# FPGA_2.net
KiCad netlist of a schematic drawn in Altium Designer
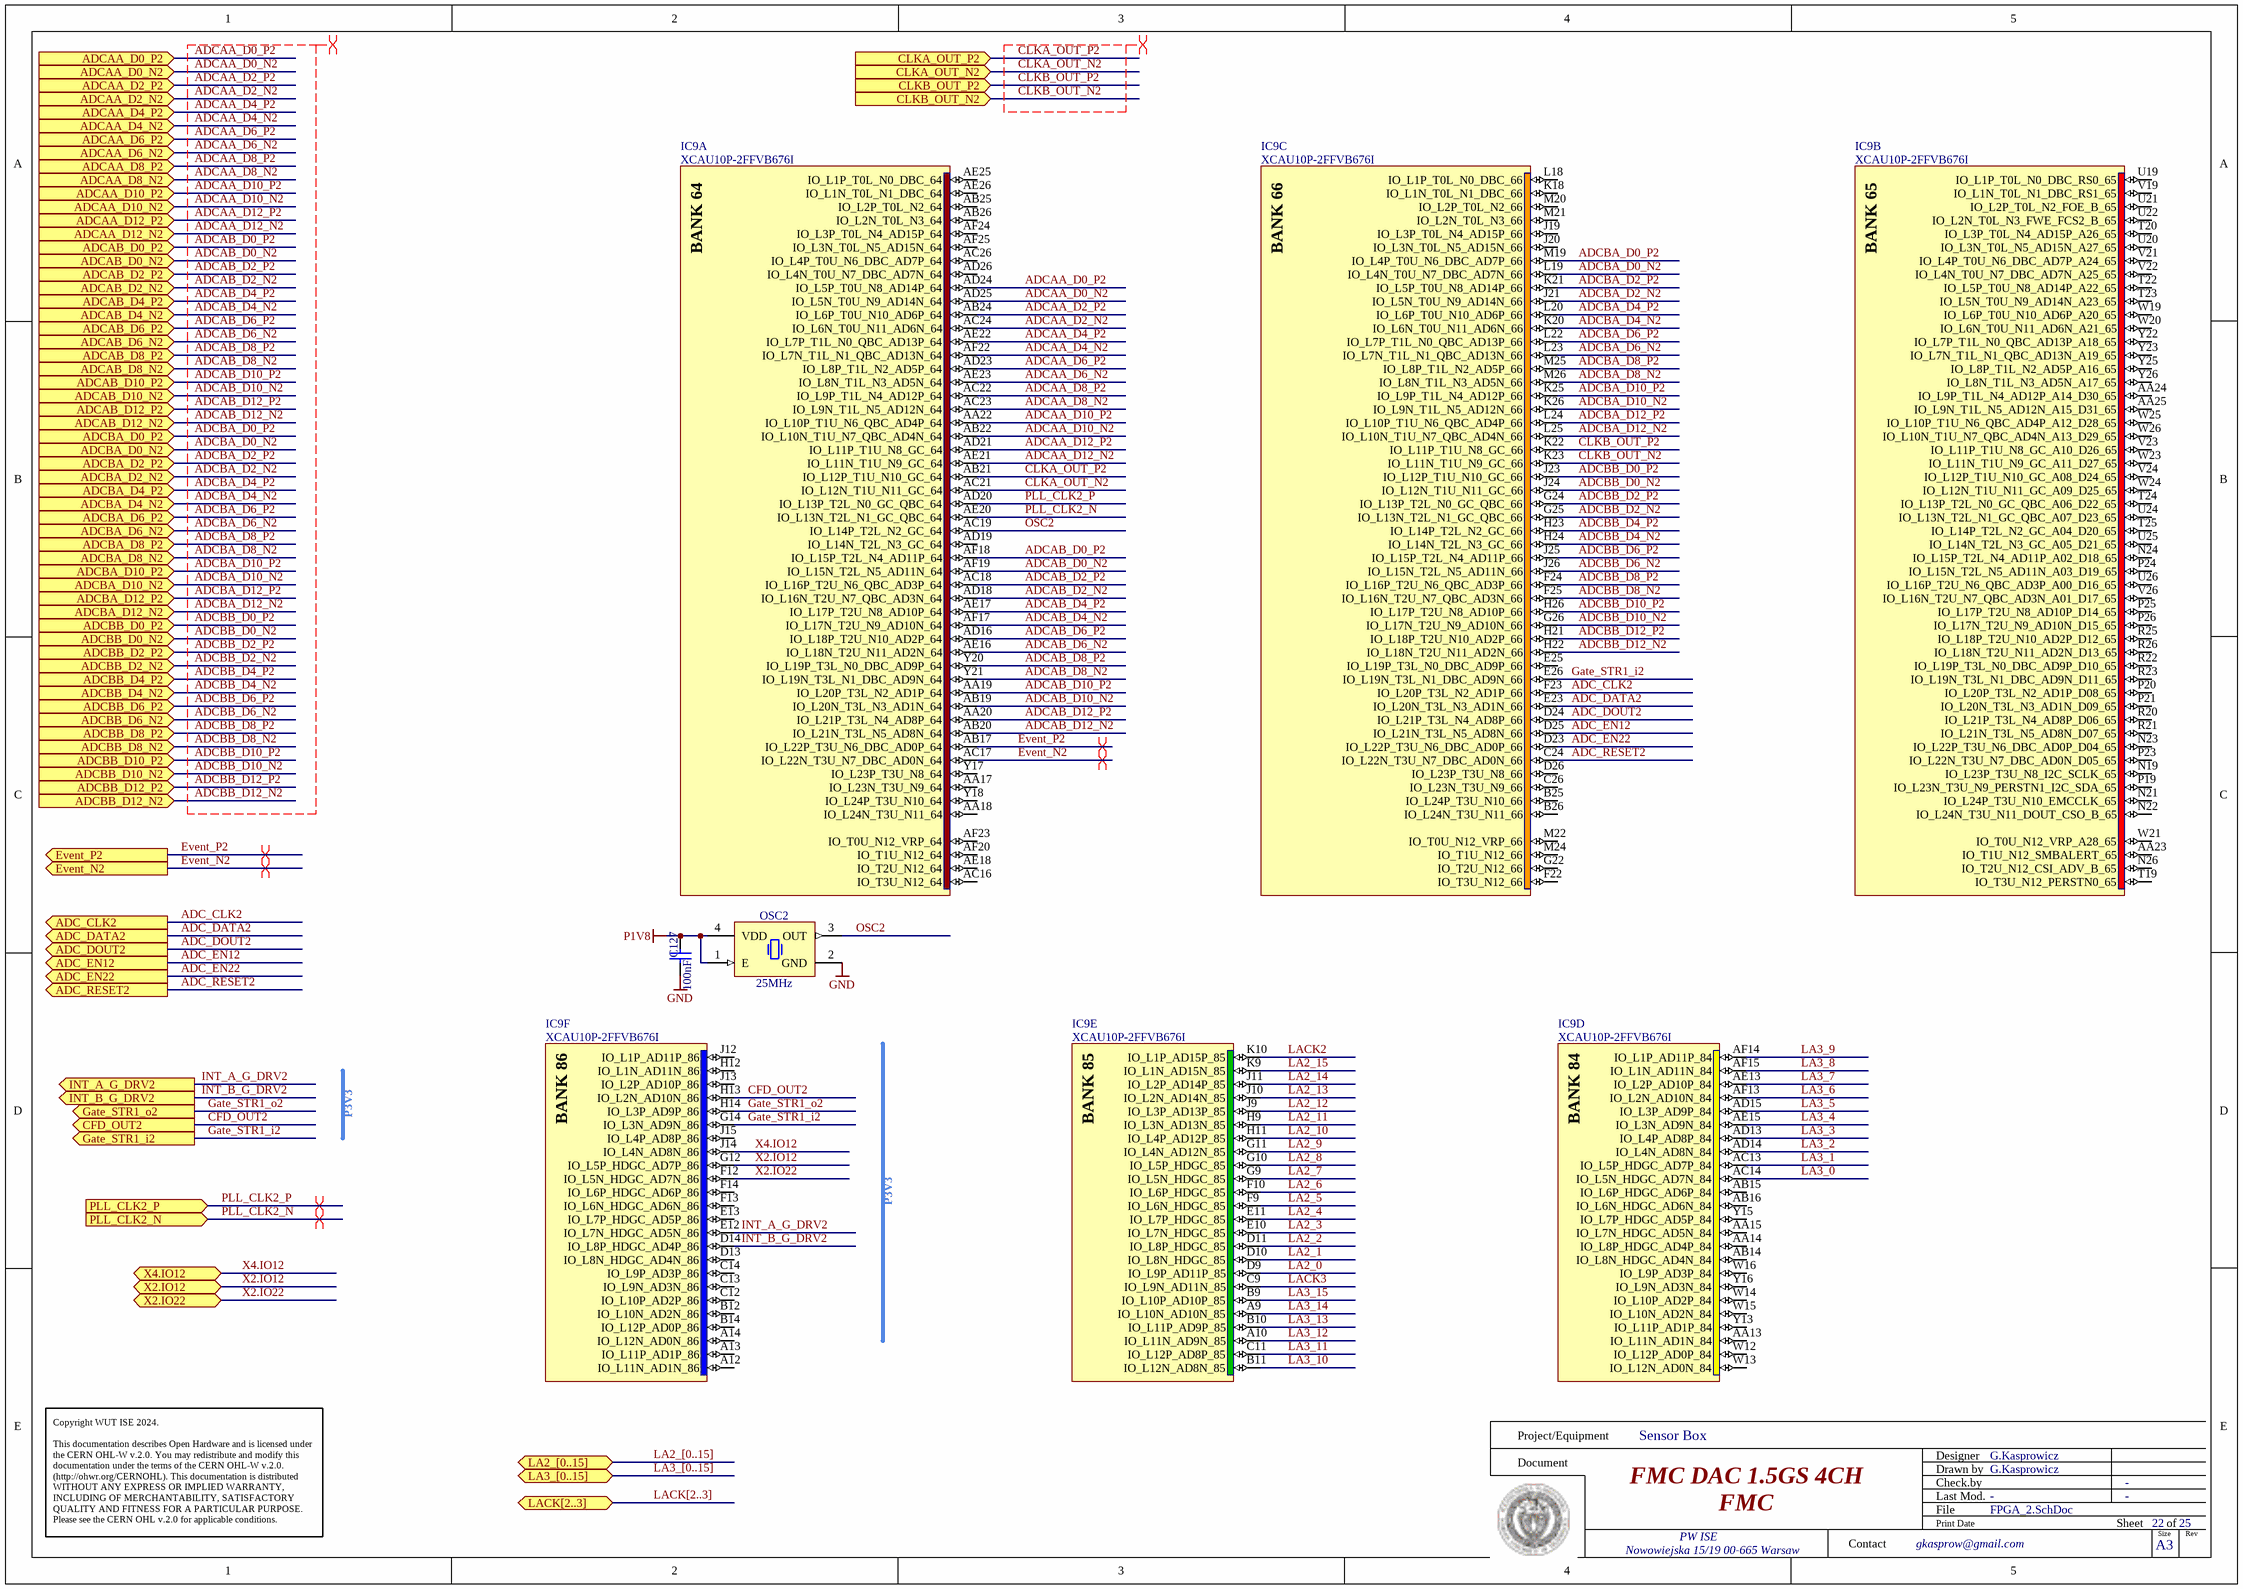
[diagram p0: FPGA_2.SchDoc]

(export (version "E")
  (design (tool "Eeschema 10.0.6"))
  (components
    (comp (ref "C127")
      (value "100nF")
      (footprint "CAPC1005X55N")
      (description "Non-polarised capacitor")
      (fields
        (field (name "PART NUMBER") "CC0402_100NF_16V_10%_X5R")
        (field (name "VOLTAGE") "16V")
        (field (name "AUTHOR") "CERN DEM JLC")
      )
      (libsource (lib "Capacitors") (part "Capacitor - non polarized"))
    )
    (comp (ref "IC9")
      (value "XCAU10P-2FFVB676I")
      (footprint "BGA676C100P26X26_2700X2700X350")
      (description "Artix UltraScale + Field Programmable Gate Array (FPGA), 676-Pin BGA, Industrial Grade")
      (fields (field (name "MANUFACTURER") "AMD") (field (name "AUTHOR") "CERN DEM HF"))
      (libsource (lib "ICs And Semiconductors") (part "XCAU10P-2FFVB676I"))
    )
    (comp (ref "OSC2")
      (value "25MHz")
      (footprint "OSC_ECS_ECS-3518")
      (description "Oscillator 4 pins 1=E/D 2=GND 3=OUT 4=VDD")
      (fields
        (field (name "PART NUMBER") "OSC_25MHZ_ECS_ECS-3518-250-B")
        (field (name "MANUFACTURER") "ECS")
        (field (name "AUTHOR") "CERN DEM JLC")
      )
      (libsource (lib "ICs And Semiconductors") (part "Oscillator 1E 2GND 3OUT 4VDD"))
    )
  )
  (nets
    (net (code "1") (name "/ADCAA_D0_N2") (class "Default")
      (node (ref "IC9") (pin "AD25") (pinfunction "IO_L5N_T0U_N9_AD14N_64_AD25") (pintype "bidirectional"))
    )
    (net (code "2") (name "/ADCAA_D0_P2") (class "Default")
      (node (ref "IC9") (pin "AD24") (pinfunction "IO_L5P_T0U_N8_AD14P_64_AD24") (pintype "bidirectional"))
    )
    (net (code "3") (name "/ADCAA_D2_N2") (class "Default")
      (node (ref "IC9") (pin "AC24") (pinfunction "IO_L6N_T0U_N11_AD6N_64_AC24") (pintype "bidirectional"))
    )
    (net (code "4") (name "/ADCAA_D2_P2") (class "Default")
      (node (ref "IC9") (pin "AB24") (pinfunction "IO_L6P_T0U_N10_AD6P_64_AB24") (pintype "bidirectional"))
    )
    (net (code "5") (name "/ADCAA_D4_N2") (class "Default")
      (node (ref "IC9") (pin "AF22") (pinfunction "IO_L7N_T1L_N1_QBC_AD13N_64_AF22") (pintype "bidirectional"))
    )
    (net (code "6") (name "/ADCAA_D4_P2") (class "Default")
      (node (ref "IC9") (pin "AE22") (pinfunction "IO_L7P_T1L_N0_QBC_AD13P_64_AE22") (pintype "bidirectional"))
    )
    (net (code "7") (name "/ADCAA_D6_N2") (class "Default")
      (node (ref "IC9") (pin "AE23") (pinfunction "IO_L8N_T1L_N3_AD5N_64_AE23") (pintype "bidirectional"))
    )
    (net (code "8") (name "/ADCAA_D6_P2") (class "Default")
      (node (ref "IC9") (pin "AD23") (pinfunction "IO_L8P_T1L_N2_AD5P_64_AD23") (pintype "bidirectional"))
    )
    (net (code "9") (name "/ADCAA_D8_N2") (class "Default")
      (node (ref "IC9") (pin "AC23") (pinfunction "IO_L9N_T1L_N5_AD12N_64_AC23") (pintype "bidirectional"))
    )
    (net (code "10") (name "/ADCAA_D8_P2") (class "Default")
      (node (ref "IC9") (pin "AC22") (pinfunction "IO_L9P_T1L_N4_AD12P_64_AC22") (pintype "bidirectional"))
    )
    (net (code "11") (name "/ADCAA_D10_N2") (class "Default")
      (node (ref "IC9") (pin "AB22") (pinfunction "IO_L10N_T1U_N7_QBC_AD4N_64_AB22") (pintype "bidirectional"))
    )
    (net (code "12") (name "/ADCAA_D10_P2") (class "Default")
      (node (ref "IC9") (pin "AA22") (pinfunction "IO_L10P_T1U_N6_QBC_AD4P_64_AA22") (pintype "bidirectional"))
    )
    (net (code "13") (name "/ADCAA_D12_N2") (class "Default")
      (node (ref "IC9") (pin "AE21") (pinfunction "IO_L11N_T1U_N9_GC_64_AE21") (pintype "bidirectional"))
    )
    (net (code "14") (name "/ADCAA_D12_P2") (class "Default")
      (node (ref "IC9") (pin "AD21") (pinfunction "IO_L11P_T1U_N8_GC_64_AD21") (pintype "bidirectional"))
    )
    (net (code "15") (name "/ADCAB_D0_N2") (class "Default")
      (node (ref "IC9") (pin "AF19") (pinfunction "IO_L15N_T2L_N5_AD11N_64_AF19") (pintype "bidirectional"))
    )
    (net (code "16") (name "/ADCAB_D0_P2") (class "Default")
      (node (ref "IC9") (pin "AF18") (pinfunction "IO_L15P_T2L_N4_AD11P_64_AF18") (pintype "bidirectional"))
    )
    (net (code "17") (name "/ADCAB_D2_N2") (class "Default")
      (node (ref "IC9") (pin "AD18") (pinfunction "IO_L16N_T2U_N7_QBC_AD3N_64_AD18") (pintype "bidirectional"))
    )
    (net (code "18") (name "/ADCAB_D2_P2") (class "Default")
      (node (ref "IC9") (pin "AC18") (pinfunction "IO_L16P_T2U_N6_QBC_AD3P_64_AC18") (pintype "bidirectional"))
    )
    (net (code "19") (name "/ADCAB_D4_N2") (class "Default")
      (node (ref "IC9") (pin "AF17") (pinfunction "IO_L17N_T2U_N9_AD10N_64_AF17") (pintype "bidirectional"))
    )
    (net (code "20") (name "/ADCAB_D4_P2") (class "Default")
      (node (ref "IC9") (pin "AE17") (pinfunction "IO_L17P_T2U_N8_AD10P_64_AE17") (pintype "bidirectional"))
    )
    (net (code "21") (name "/ADCAB_D6_N2") (class "Default")
      (node (ref "IC9") (pin "AE16") (pinfunction "IO_L18N_T2U_N11_AD2N_64_AE16") (pintype "bidirectional"))
    )
    (net (code "22") (name "/ADCAB_D6_P2") (class "Default")
      (node (ref "IC9") (pin "AD16") (pinfunction "IO_L18P_T2U_N10_AD2P_64_AD16") (pintype "bidirectional"))
    )
    (net (code "23") (name "/ADCAB_D8_N2") (class "Default")
      (node (ref "IC9") (pin "Y21") (pinfunction "IO_L19N_T3L_N1_DBC_AD9N_64_Y21") (pintype "bidirectional"))
    )
    (net (code "24") (name "/ADCAB_D8_P2") (class "Default")
      (node (ref "IC9") (pin "Y20") (pinfunction "IO_L19P_T3L_N0_DBC_AD9P_64_Y20") (pintype "bidirectional"))
    )
    (net (code "25") (name "/ADCAB_D10_N2") (class "Default")
      (node (ref "IC9") (pin "AB19") (pinfunction "IO_L20N_T3L_N3_AD1N_64_AB19") (pintype "bidirectional"))
    )
    (net (code "26") (name "/ADCAB_D10_P2") (class "Default")
      (node (ref "IC9") (pin "AA19") (pinfunction "IO_L20P_T3L_N2_AD1P_64_AA19") (pintype "bidirectional"))
    )
    (net (code "27") (name "/ADCAB_D12_N2") (class "Default")
      (node (ref "IC9") (pin "AB20") (pinfunction "IO_L21N_T3L_N5_AD8N_64_AB20") (pintype "bidirectional"))
    )
    (net (code "28") (name "/ADCAB_D12_P2") (class "Default")
      (node (ref "IC9") (pin "AA20") (pinfunction "IO_L21P_T3L_N4_AD8P_64_AA20") (pintype "bidirectional"))
    )
    (net (code "29") (name "/ADCBA_D0_N2") (class "Default")
      (node (ref "IC9") (pin "L19") (pinfunction "IO_L4N_T0U_N7_DBC_AD7N_66_L19") (pintype "bidirectional"))
    )
    (net (code "30") (name "/ADCBA_D0_P2") (class "Default")
      (node (ref "IC9") (pin "M19") (pinfunction "IO_L4P_T0U_N6_DBC_AD7P_66_M19") (pintype "bidirectional"))
    )
    (net (code "31") (name "/ADCBA_D2_N2") (class "Default")
      (node (ref "IC9") (pin "J21") (pinfunction "IO_L5N_T0U_N9_AD14N_66_J21") (pintype "bidirectional"))
    )
    (net (code "32") (name "/ADCBA_D2_P2") (class "Default")
      (node (ref "IC9") (pin "K21") (pinfunction "IO_L5P_T0U_N8_AD14P_66_K21") (pintype "bidirectional"))
    )
    (net (code "33") (name "/ADCBA_D4_N2") (class "Default")
      (node (ref "IC9") (pin "K20") (pinfunction "IO_L6N_T0U_N11_AD6N_66_K20") (pintype "bidirectional"))
    )
    (net (code "34") (name "/ADCBA_D4_P2") (class "Default")
      (node (ref "IC9") (pin "L20") (pinfunction "IO_L6P_T0U_N10_AD6P_66_L20") (pintype "bidirectional"))
    )
    (net (code "35") (name "/ADCBA_D6_N2") (class "Default")
      (node (ref "IC9") (pin "L23") (pinfunction "IO_L7N_T1L_N1_QBC_AD13N_66_L23") (pintype "bidirectional"))
    )
    (net (code "36") (name "/ADCBA_D6_P2") (class "Default")
      (node (ref "IC9") (pin "L22") (pinfunction "IO_L7P_T1L_N0_QBC_AD13P_66_L22") (pintype "bidirectional"))
    )
    (net (code "37") (name "/ADCBA_D8_N2") (class "Default")
      (node (ref "IC9") (pin "M26") (pinfunction "IO_L8N_T1L_N3_AD5N_66_M26") (pintype "bidirectional"))
    )
    (net (code "38") (name "/ADCBA_D8_P2") (class "Default")
      (node (ref "IC9") (pin "M25") (pinfunction "IO_L8P_T1L_N2_AD5P_66_M25") (pintype "bidirectional"))
    )
    (net (code "39") (name "/ADCBA_D10_N2") (class "Default")
      (node (ref "IC9") (pin "K26") (pinfunction "IO_L9N_T1L_N5_AD12N_66_K26") (pintype "bidirectional"))
    )
    (net (code "40") (name "/ADCBA_D10_P2") (class "Default")
      (node (ref "IC9") (pin "K25") (pinfunction "IO_L9P_T1L_N4_AD12P_66_K25") (pintype "bidirectional"))
    )
    (net (code "41") (name "/ADCBA_D12_N2") (class "Default")
      (node (ref "IC9") (pin "L25") (pinfunction "IO_L10N_T1U_N7_QBC_AD4N_66_L25") (pintype "bidirectional"))
    )
    (net (code "42") (name "/ADCBA_D12_P2") (class "Default")
      (node (ref "IC9") (pin "L24") (pinfunction "IO_L10P_T1U_N6_QBC_AD4P_66_L24") (pintype "bidirectional"))
    )
    (net (code "43") (name "/ADCBB_D0_N2") (class "Default")
      (node (ref "IC9") (pin "J24") (pinfunction "IO_L12N_T1U_N11_GC_66_J24") (pintype "bidirectional"))
    )
    (net (code "44") (name "/ADCBB_D0_P2") (class "Default")
      (node (ref "IC9") (pin "J23") (pinfunction "IO_L12P_T1U_N10_GC_66_J23") (pintype "bidirectional"))
    )
    (net (code "45") (name "/ADCBB_D2_N2") (class "Default")
      (node (ref "IC9") (pin "G25") (pinfunction "IO_L13N_T2L_N1_GC_QBC_66_G25") (pintype "bidirectional"))
    )
    (net (code "46") (name "/ADCBB_D2_P2") (class "Default")
      (node (ref "IC9") (pin "G24") (pinfunction "IO_L13P_T2L_N0_GC_QBC_66_G24") (pintype "bidirectional"))
    )
    (net (code "47") (name "/ADCBB_D4_N2") (class "Default")
      (node (ref "IC9") (pin "H24") (pinfunction "IO_L14N_T2L_N3_GC_66_H24") (pintype "bidirectional"))
    )
    (net (code "48") (name "/ADCBB_D4_P2") (class "Default")
      (node (ref "IC9") (pin "H23") (pinfunction "IO_L14P_T2L_N2_GC_66_H23") (pintype "bidirectional"))
    )
    (net (code "49") (name "/ADCBB_D6_N2") (class "Default")
      (node (ref "IC9") (pin "J26") (pinfunction "IO_L15N_T2L_N5_AD11N_66_J26") (pintype "bidirectional"))
    )
    (net (code "50") (name "/ADCBB_D6_P2") (class "Default")
      (node (ref "IC9") (pin "J25") (pinfunction "IO_L15P_T2L_N4_AD11P_66_J25") (pintype "bidirectional"))
    )
    (net (code "51") (name "/ADCBB_D8_N2") (class "Default")
      (node (ref "IC9") (pin "F25") (pinfunction "IO_L16N_T2U_N7_QBC_AD3N_66_F25") (pintype "bidirectional"))
    )
    (net (code "52") (name "/ADCBB_D8_P2") (class "Default")
      (node (ref "IC9") (pin "F24") (pinfunction "IO_L16P_T2U_N6_QBC_AD3P_66_F24") (pintype "bidirectional"))
    )
    (net (code "53") (name "/ADCBB_D10_N2") (class "Default")
      (node (ref "IC9") (pin "G26") (pinfunction "IO_L17N_T2U_N9_AD10N_66_G26") (pintype "bidirectional"))
    )
    (net (code "54") (name "/ADCBB_D10_P2") (class "Default")
      (node (ref "IC9") (pin "H26") (pinfunction "IO_L17P_T2U_N8_AD10P_66_H26") (pintype "bidirectional"))
    )
    (net (code "55") (name "/ADCBB_D12_N2") (class "Default")
      (node (ref "IC9") (pin "H22") (pinfunction "IO_L18N_T2U_N11_AD2N_66_H22") (pintype "bidirectional"))
    )
    (net (code "56") (name "/ADCBB_D12_P2") (class "Default")
      (node (ref "IC9") (pin "H21") (pinfunction "IO_L18P_T2U_N10_AD2P_66_H21") (pintype "bidirectional"))
    )
    (net (code "57") (name "/ADC_CLK2") (class "Default")
      (node (ref "IC9") (pin "F23") (pinfunction "IO_L20P_T3L_N2_AD1P_66_F23") (pintype "bidirectional"))
    )
    (net (code "58") (name "/ADC_DATA2") (class "Default")
      (node (ref "IC9") (pin "E23") (pinfunction "IO_L20N_T3L_N3_AD1N_66_E23") (pintype "bidirectional"))
    )
    (net (code "59") (name "/ADC_DOUT2") (class "Default")
      (node (ref "IC9") (pin "D24") (pinfunction "IO_L21P_T3L_N4_AD8P_66_D24") (pintype "bidirectional"))
    )
    (net (code "60") (name "/ADC_EN12") (class "Default")
      (node (ref "IC9") (pin "D25") (pinfunction "IO_L21N_T3L_N5_AD8N_66_D25") (pintype "bidirectional"))
    )
    (net (code "61") (name "/ADC_EN22") (class "Default")
      (node (ref "IC9") (pin "D23") (pinfunction "IO_L22P_T3U_N6_DBC_AD0P_66_D23") (pintype "bidirectional"))
    )
    (net (code "62") (name "/ADC_RESET2") (class "Default")
      (node (ref "IC9") (pin "C24") (pinfunction "IO_L22N_T3U_N7_DBC_AD0N_66_C24") (pintype "bidirectional"))
    )
    (net (code "63") (name "/CFD_OUT2") (class "Default")
      (node (ref "IC9") (pin "H13") (pinfunction "IO_L2N_AD10N_86_H13") (pintype "bidirectional"))
    )
    (net (code "64") (name "/CLKA_OUT_N2") (class "Default")
      (node (ref "IC9") (pin "AC21") (pinfunction "IO_L12N_T1U_N11_GC_64_AC21") (pintype "bidirectional"))
    )
    (net (code "65") (name "/CLKA_OUT_P2") (class "Default")
      (node (ref "IC9") (pin "AB21") (pinfunction "IO_L12P_T1U_N10_GC_64_AB21") (pintype "bidirectional"))
    )
    (net (code "66") (name "/CLKB_OUT_N2") (class "Default")
      (node (ref "IC9") (pin "K23") (pinfunction "IO_L11N_T1U_N9_GC_66_K23") (pintype "bidirectional"))
    )
    (net (code "67") (name "/CLKB_OUT_P2") (class "Default")
      (node (ref "IC9") (pin "K22") (pinfunction "IO_L11P_T1U_N8_GC_66_K22") (pintype "bidirectional"))
    )
    (net (code "68") (name "/Event_N2") (class "Default")
      (node (ref "IC9") (pin "AC17") (pinfunction "IO_L22N_T3U_N7_DBC_AD0N_64_AC17") (pintype "bidirectional"))
    )
    (net (code "69") (name "/Event_P2") (class "Default")
      (node (ref "IC9") (pin "AB17") (pinfunction "IO_L22P_T3U_N6_DBC_AD0P_64_AB17") (pintype "bidirectional"))
    )
    (net (code "70") (name "/Gate_STR1_i2") (class "Default")
      (node (ref "IC9") (pin "E26") (pinfunction "IO_L19N_T3L_N1_DBC_AD9N_66_E26") (pintype "bidirectional"))
      (node (ref "IC9") (pin "G14") (pinfunction "IO_L3N_AD9N_86_G14") (pintype "bidirectional"))
    )
    (net (code "71") (name "/Gate_STR1_o2") (class "Default")
      (node (ref "IC9") (pin "H14") (pinfunction "IO_L3P_AD9P_86_H14") (pintype "bidirectional"))
    )
    (net (code "72") (name "/INT_A_G_DRV2") (class "Default")
      (node (ref "IC9") (pin "E12") (pinfunction "IO_L7N_HDGC_AD5N_86_E12") (pintype "bidirectional"))
    )
    (net (code "73") (name "/INT_B_G_DRV2") (class "Default")
      (node (ref "IC9") (pin "D14") (pinfunction "IO_L8P_HDGC_AD4P_86_D14") (pintype "bidirectional"))
    )
    (net (code "74") (name "/LA2_0") (class "Default")
      (node (ref "IC9") (pin "D9") (pinfunction "IO_L9P_AD11P_85_D9") (pintype "bidirectional"))
    )
    (net (code "75") (name "/LA2_1") (class "Default")
      (node (ref "IC9") (pin "D10") (pinfunction "IO_L8N_HDGC_85_D10") (pintype "bidirectional"))
    )
    (net (code "76") (name "/LA2_2") (class "Default")
      (node (ref "IC9") (pin "D11") (pinfunction "IO_L8P_HDGC_85_D11") (pintype "bidirectional"))
    )
    (net (code "77") (name "/LA2_3") (class "Default")
      (node (ref "IC9") (pin "E10") (pinfunction "IO_L7N_HDGC_85_E10") (pintype "bidirectional"))
    )
    (net (code "78") (name "/LA2_4") (class "Default")
      (node (ref "IC9") (pin "E11") (pinfunction "IO_L7P_HDGC_85_E11") (pintype "bidirectional"))
    )
    (net (code "79") (name "/LA2_5") (class "Default")
      (node (ref "IC9") (pin "F9") (pinfunction "IO_L6N_HDGC_85_F9") (pintype "bidirectional"))
    )
    (net (code "80") (name "/LA2_6") (class "Default")
      (node (ref "IC9") (pin "F10") (pinfunction "IO_L6P_HDGC_85_F10") (pintype "bidirectional"))
    )
    (net (code "81") (name "/LA2_7") (class "Default")
      (node (ref "IC9") (pin "G9") (pinfunction "IO_L5N_HDGC_85_G9") (pintype "bidirectional"))
    )
    (net (code "82") (name "/LA2_8") (class "Default")
      (node (ref "IC9") (pin "G10") (pinfunction "IO_L5P_HDGC_85_G10") (pintype "bidirectional"))
    )
    (net (code "83") (name "/LA2_9") (class "Default")
      (node (ref "IC9") (pin "G11") (pinfunction "IO_L4N_AD12N_85_G11") (pintype "bidirectional"))
    )
    (net (code "84") (name "/LA2_10") (class "Default")
      (node (ref "IC9") (pin "H11") (pinfunction "IO_L4P_AD12P_85_H11") (pintype "bidirectional"))
    )
    (net (code "85") (name "/LA2_11") (class "Default")
      (node (ref "IC9") (pin "H9") (pinfunction "IO_L3N_AD13N_85_H9") (pintype "bidirectional"))
    )
    (net (code "86") (name "/LA2_12") (class "Default")
      (node (ref "IC9") (pin "J9") (pinfunction "IO_L3P_AD13P_85_J9") (pintype "bidirectional"))
    )
    (net (code "87") (name "/LA2_13") (class "Default")
      (node (ref "IC9") (pin "J10") (pinfunction "IO_L2N_AD14N_85_J10") (pintype "bidirectional"))
    )
    (net (code "88") (name "/LA2_14") (class "Default")
      (node (ref "IC9") (pin "J11") (pinfunction "IO_L2P_AD14P_85_J11") (pintype "bidirectional"))
    )
    (net (code "89") (name "/LA2_15") (class "Default")
      (node (ref "IC9") (pin "K9") (pinfunction "IO_L1N_AD15N_85_K9") (pintype "bidirectional"))
    )
    (net (code "91") (name "/LA3_0") (class "Default")
      (node (ref "IC9") (pin "AC14") (pinfunction "IO_L5N_HDGC_AD7N_84_AC14") (pintype "bidirectional"))
    )
    (net (code "92") (name "/LA3_1") (class "Default")
      (node (ref "IC9") (pin "AC13") (pinfunction "IO_L5P_HDGC_AD7P_84_AC13") (pintype "bidirectional"))
    )
    (net (code "93") (name "/LA3_2") (class "Default")
      (node (ref "IC9") (pin "AD14") (pinfunction "IO_L4N_AD8N_84_AD14") (pintype "bidirectional"))
    )
    (net (code "94") (name "/LA3_3") (class "Default")
      (node (ref "IC9") (pin "AD13") (pinfunction "IO_L4P_AD8P_84_AD13") (pintype "bidirectional"))
    )
    (net (code "95") (name "/LA3_4") (class "Default")
      (node (ref "IC9") (pin "AE15") (pinfunction "IO_L3N_AD9N_84_AE15") (pintype "bidirectional"))
    )
    (net (code "96") (name "/LA3_5") (class "Default")
      (node (ref "IC9") (pin "AD15") (pinfunction "IO_L3P_AD9P_84_AD15") (pintype "bidirectional"))
    )
    (net (code "97") (name "/LA3_6") (class "Default")
      (node (ref "IC9") (pin "AF13") (pinfunction "IO_L2N_AD10N_84_AF13") (pintype "bidirectional"))
    )
    (net (code "98") (name "/LA3_7") (class "Default")
      (node (ref "IC9") (pin "AE13") (pinfunction "IO_L2P_AD10P_84_AE13") (pintype "bidirectional"))
    )
    (net (code "99") (name "/LA3_8") (class "Default")
      (node (ref "IC9") (pin "AF15") (pinfunction "IO_L1N_AD11N_84_AF15") (pintype "bidirectional"))
    )
    (net (code "100") (name "/LA3_9") (class "Default")
      (node (ref "IC9") (pin "AF14") (pinfunction "IO_L1P_AD11P_84_AF14") (pintype "bidirectional"))
    )
    (net (code "101") (name "/LA3_10") (class "Default")
      (node (ref "IC9") (pin "B11") (pinfunction "IO_L12N_AD8N_85_B11") (pintype "bidirectional"))
    )
    (net (code "102") (name "/LA3_11") (class "Default")
      (node (ref "IC9") (pin "C11") (pinfunction "IO_L12P_AD8P_85_C11") (pintype "bidirectional"))
    )
    (net (code "103") (name "/LA3_12") (class "Default")
      (node (ref "IC9") (pin "A10") (pinfunction "IO_L11N_AD9N_85_A10") (pintype "bidirectional"))
    )
    (net (code "104") (name "/LA3_13") (class "Default")
      (node (ref "IC9") (pin "B10") (pinfunction "IO_L11P_AD9P_85_B10") (pintype "bidirectional"))
    )
    (net (code "105") (name "/LA3_14") (class "Default")
      (node (ref "IC9") (pin "A9") (pinfunction "IO_L10N_AD10N_85_A9") (pintype "bidirectional"))
    )
    (net (code "106") (name "/LA3_15") (class "Default")
      (node (ref "IC9") (pin "B9") (pinfunction "IO_L10P_AD10P_85_B9") (pintype "bidirectional"))
    )
    (net (code "108") (name "/LACK2") (class "Default")
      (node (ref "IC9") (pin "K10") (pinfunction "IO_L1P_AD15P_85_K10") (pintype "bidirectional"))
    )
    (net (code "109") (name "/LACK3") (class "Default")
      (node (ref "IC9") (pin "C9") (pinfunction "IO_L9N_AD11N_85_C9") (pintype "bidirectional"))
    )
    (net (code "111") (name "/OSC2") (class "Default")
      (node (ref "IC9") (pin "AC19") (pinfunction "IO_L14P_T2L_N2_GC_64_AC19") (pintype "bidirectional"))
      (node (ref "OSC2") (pin "3") (pinfunction "OUT_3") (pintype "output"))
    )
    (net (code "112") (name "/PLL_CLK2_N") (class "Default")
      (node (ref "IC9") (pin "AE20") (pinfunction "IO_L13N_T2L_N1_GC_QBC_64_AE20") (pintype "bidirectional"))
    )
    (net (code "113") (name "/PLL_CLK2_P") (class "Default")
      (node (ref "IC9") (pin "AD20") (pinfunction "IO_L13P_T2L_N0_GC_QBC_64_AD20") (pintype "bidirectional"))
    )
    (net (code "114") (name "/X2.IO12") (class "Default")
      (node (ref "IC9") (pin "G12") (pinfunction "IO_L5P_HDGC_AD7P_86_G12") (pintype "bidirectional"))
    )
    (net (code "115") (name "/X2.IO22") (class "Default")
      (node (ref "IC9") (pin "F12") (pinfunction "IO_L5N_HDGC_AD7N_86_F12") (pintype "bidirectional"))
    )
    (net (code "116") (name "/X4.IO12") (class "Default")
      (node (ref "IC9") (pin "J14") (pinfunction "IO_L4N_AD8N_86_J14") (pintype "bidirectional"))
    )
    (net (code "117") (name "GND") (class "Default")
      (node (ref "C127") (pin "1") (pinfunction "1_1") (pintype "passive"))
      (node (ref "OSC2") (pin "2") (pinfunction "GND_2") (pintype "power_in"))
    )
    (net (code "118") (name "P1V8") (class "Default")
      (node (ref "C127") (pin "2") (pinfunction "2_2") (pintype "passive"))
      (node (ref "OSC2") (pin "1") (pinfunction "E_1") (pintype "input"))
      (node (ref "OSC2") (pin "4") (pinfunction "VDD_4") (pintype "power_in"))
    )
    (net (code "119") (name "unconnected-(IC9A-IO_L1N_T0L_N1_DBC_64-PadAE26)") (class "Default")
      (node (ref "IC9") (pin "AE26") (pinfunction "IO_L1N_T0L_N1_DBC_64_AE26") (pintype "bidirectional"))
    )
    (net (code "120") (name "unconnected-(IC9A-IO_L1P_T0L_N0_DBC_64-PadAE25)") (class "Default")
      (node (ref "IC9") (pin "AE25") (pinfunction "IO_L1P_T0L_N0_DBC_64_AE25") (pintype "bidirectional"))
    )
    (net (code "121") (name "unconnected-(IC9A-IO_L2N_T0L_N3_64-PadAB26)") (class "Default")
      (node (ref "IC9") (pin "AB26") (pinfunction "IO_L2N_T0L_N3_64_AB26") (pintype "bidirectional"))
    )
    (net (code "122") (name "unconnected-(IC9A-IO_L2P_T0L_N2_64-PadAB25)") (class "Default")
      (node (ref "IC9") (pin "AB25") (pinfunction "IO_L2P_T0L_N2_64_AB25") (pintype "bidirectional"))
    )
    (net (code "123") (name "unconnected-(IC9A-IO_L3N_T0L_N5_AD15N_64-PadAF25)") (class "Default")
      (node (ref "IC9") (pin "AF25") (pinfunction "IO_L3N_T0L_N5_AD15N_64_AF25") (pintype "bidirectional"))
    )
    (net (code "124") (name "unconnected-(IC9A-IO_L3P_T0L_N4_AD15P_64-PadAF24)") (class "Default")
      (node (ref "IC9") (pin "AF24") (pinfunction "IO_L3P_T0L_N4_AD15P_64_AF24") (pintype "bidirectional"))
    )
    (net (code "125") (name "unconnected-(IC9A-IO_L4N_T0U_N7_DBC_AD7N_64-PadAD26)") (class "Default")
      (node (ref "IC9") (pin "AD26") (pinfunction "IO_L4N_T0U_N7_DBC_AD7N_64_AD26") (pintype "bidirectional"))
    )
    (net (code "126") (name "unconnected-(IC9A-IO_L4P_T0U_N6_DBC_AD7P_64-PadAC26)") (class "Default")
      (node (ref "IC9") (pin "AC26") (pinfunction "IO_L4P_T0U_N6_DBC_AD7P_64_AC26") (pintype "bidirectional"))
    )
    (net (code "127") (name "unconnected-(IC9A-IO_L14N_T2L_N3_GC_64-PadAD19)") (class "Default")
      (node (ref "IC9") (pin "AD19") (pinfunction "IO_L14N_T2L_N3_GC_64_AD19") (pintype "bidirectional"))
    )
    (net (code "128") (name "unconnected-(IC9A-IO_L23N_T3U_N9_64-PadAA17)") (class "Default")
      (node (ref "IC9") (pin "AA17") (pinfunction "IO_L23N_T3U_N9_64_AA17") (pintype "bidirectional"))
    )
    (net (code "129") (name "unconnected-(IC9A-IO_L23P_T3U_N8_64-PadY17)") (class "Default")
      (node (ref "IC9") (pin "Y17") (pinfunction "IO_L23P_T3U_N8_64_Y17") (pintype "bidirectional"))
    )
    (net (code "130") (name "unconnected-(IC9A-IO_L24N_T3U_N11_64-PadAA18)") (class "Default")
      (node (ref "IC9") (pin "AA18") (pinfunction "IO_L24N_T3U_N11_64_AA18") (pintype "bidirectional"))
    )
    (net (code "131") (name "unconnected-(IC9A-IO_L24P_T3U_N10_64-PadY18)") (class "Default")
      (node (ref "IC9") (pin "Y18") (pinfunction "IO_L24P_T3U_N10_64_Y18") (pintype "bidirectional"))
    )
    (net (code "132") (name "unconnected-(IC9A-IO_T0U_N12_VRP_64-PadAF23)") (class "Default")
      (node (ref "IC9") (pin "AF23") (pinfunction "IO_T0U_N12_VRP_64_AF23") (pintype "bidirectional"))
    )
    (net (code "133") (name "unconnected-(IC9A-IO_T1U_N12_64-PadAF20)") (class "Default")
      (node (ref "IC9") (pin "AF20") (pinfunction "IO_T1U_N12_64_AF20") (pintype "bidirectional"))
    )
    (net (code "134") (name "unconnected-(IC9A-IO_T2U_N12_64-PadAE18)") (class "Default")
      (node (ref "IC9") (pin "AE18") (pinfunction "IO_T2U_N12_64_AE18") (pintype "bidirectional"))
    )
    (net (code "135") (name "unconnected-(IC9A-IO_T3U_N12_64-PadAC16)") (class "Default")
      (node (ref "IC9") (pin "AC16") (pinfunction "IO_T3U_N12_64_AC16") (pintype "bidirectional"))
    )
    (net (code "136") (name "unconnected-(IC9B-IO_L1N_T0L_N1_DBC_RS1_65-PadV19)") (class "Default")
      (node (ref "IC9") (pin "V19") (pinfunction "IO_L1N_T0L_N1_DBC_RS1_65_V19") (pintype "bidirectional"))
    )
    (net (code "137") (name "unconnected-(IC9B-IO_L1P_T0L_N0_DBC_RS0_65-PadU19)") (class "Default")
      (node (ref "IC9") (pin "U19") (pinfunction "IO_L1P_T0L_N0_DBC_RS0_65_U19") (pintype "bidirectional"))
    )
    (net (code "138") (name "unconnected-(IC9B-IO_L2N_T0L_N3_FWE_FCS2_B_65-PadU22)") (class "Default")
      (node (ref "IC9") (pin "U22") (pinfunction "IO_L2N_T0L_N3_FWE_FCS2_B_65_U22") (pintype "bidirectional"))
    )
    (net (code "139") (name "unconnected-(IC9B-IO_L2P_T0L_N2_FOE_B_65-PadU21)") (class "Default")
      (node (ref "IC9") (pin "U21") (pinfunction "IO_L2P_T0L_N2_FOE_B_65_U21") (pintype "bidirectional"))
    )
    (net (code "140") (name "unconnected-(IC9B-IO_L3N_T0L_N5_AD15N_A27_65-PadU20)") (class "Default")
      (node (ref "IC9") (pin "U20") (pinfunction "IO_L3N_T0L_N5_AD15N_A27_65_U20") (pintype "bidirectional"))
    )
    (net (code "141") (name "unconnected-(IC9B-IO_L3P_T0L_N4_AD15P_A26_65-PadT20)") (class "Default")
      (node (ref "IC9") (pin "T20") (pinfunction "IO_L3P_T0L_N4_AD15P_A26_65_T20") (pintype "bidirectional"))
    )
    (net (code "142") (name "unconnected-(IC9B-IO_L4N_T0U_N7_DBC_AD7N_A25_65-PadV22)") (class "Default")
      (node (ref "IC9") (pin "V22") (pinfunction "IO_L4N_T0U_N7_DBC_AD7N_A25_65_V22") (pintype "bidirectional"))
    )
    (net (code "143") (name "unconnected-(IC9B-IO_L4P_T0U_N6_DBC_AD7P_A24_65-PadV21)") (class "Default")
      (node (ref "IC9") (pin "V21") (pinfunction "IO_L4P_T0U_N6_DBC_AD7P_A24_65_V21") (pintype "bidirectional"))
    )
    (net (code "144") (name "unconnected-(IC9B-IO_L5N_T0U_N9_AD14N_A23_65-PadT23)") (class "Default")
      (node (ref "IC9") (pin "T23") (pinfunction "IO_L5N_T0U_N9_AD14N_A23_65_T23") (pintype "bidirectional"))
    )
    (net (code "145") (name "unconnected-(IC9B-IO_L5P_T0U_N8_AD14P_A22_65-PadT22)") (class "Default")
      (node (ref "IC9") (pin "T22") (pinfunction "IO_L5P_T0U_N8_AD14P_A22_65_T22") (pintype "bidirectional"))
    )
    (net (code "146") (name "unconnected-(IC9B-IO_L6N_T0U_N11_AD6N_A21_65-PadW20)") (class "Default")
      (node (ref "IC9") (pin "W20") (pinfunction "IO_L6N_T0U_N11_AD6N_A21_65_W20") (pintype "bidirectional"))
    )
    (net (code "147") (name "unconnected-(IC9B-IO_L6P_T0U_N10_AD6P_A20_65-PadW19)") (class "Default")
      (node (ref "IC9") (pin "W19") (pinfunction "IO_L6P_T0U_N10_AD6P_A20_65_W19") (pintype "bidirectional"))
    )
    (net (code "148") (name "unconnected-(IC9B-IO_L7N_T1L_N1_QBC_AD13N_A19_65-PadY23)") (class "Default")
      (node (ref "IC9") (pin "Y23") (pinfunction "IO_L7N_T1L_N1_QBC_AD13N_A19_65_Y23") (pintype "bidirectional"))
    )
    (net (code "149") (name "unconnected-(IC9B-IO_L7P_T1L_N0_QBC_AD13P_A18_65-PadY22)") (class "Default")
      (node (ref "IC9") (pin "Y22") (pinfunction "IO_L7P_T1L_N0_QBC_AD13P_A18_65_Y22") (pintype "bidirectional"))
    )
    (net (code "150") (name "unconnected-(IC9B-IO_L8N_T1L_N3_AD5N_A17_65-PadY26)") (class "Default")
      (node (ref "IC9") (pin "Y26") (pinfunction "IO_L8N_T1L_N3_AD5N_A17_65_Y26") (pintype "bidirectional"))
    )
    (net (code "151") (name "unconnected-(IC9B-IO_L8P_T1L_N2_AD5P_A16_65-PadY25)") (class "Default")
      (node (ref "IC9") (pin "Y25") (pinfunction "IO_L8P_T1L_N2_AD5P_A16_65_Y25") (pintype "bidirectional"))
    )
    (net (code "152") (name "unconnected-(IC9B-IO_L9N_T1L_N5_AD12N_A15_D31_65-PadAA25)") (class "Default")
      (node (ref "IC9") (pin "AA25") (pinfunction "IO_L9N_T1L_N5_AD12N_A15_D31_65_AA25") (pintype "bidirectional"))
    )
    (net (code "153") (name "unconnected-(IC9B-IO_L9P_T1L_N4_AD12P_A14_D30_65-PadAA24)") (class "Default")
      (node (ref "IC9") (pin "AA24") (pinfunction "IO_L9P_T1L_N4_AD12P_A14_D30_65_AA24") (pintype "bidirectional"))
    )
    (net (code "154") (name "unconnected-(IC9B-IO_L10N_T1U_N7_QBC_AD4N_A13_D29_65-PadW26)") (class "Default")
      (node (ref "IC9") (pin "W26") (pinfunction "IO_L10N_T1U_N7_QBC_AD4N_A13_D29_65_W26") (pintype "bidirectional"))
    )
    (net (code "155") (name "unconnected-(IC9B-IO_L10P_T1U_N6_QBC_AD4P_A12_D28_65-PadW25)") (class "Default")
      (node (ref "IC9") (pin "W25") (pinfunction "IO_L10P_T1U_N6_QBC_AD4P_A12_D28_65_W25") (pintype "bidirectional"))
    )
    (net (code "156") (name "unconnected-(IC9B-IO_L11N_T1U_N9_GC_A11_D27_65-PadW23)") (class "Default")
      (node (ref "IC9") (pin "W23") (pinfunction "IO_L11N_T1U_N9_GC_A11_D27_65_W23") (pintype "bidirectional"))
    )
    (net (code "157") (name "unconnected-(IC9B-IO_L11P_T1U_N8_GC_A10_D26_65-PadV23)") (class "Default")
      (node (ref "IC9") (pin "V23") (pinfunction "IO_L11P_T1U_N8_GC_A10_D26_65_V23") (pintype "bidirectional"))
    )
    (net (code "158") (name "unconnected-(IC9B-IO_L12N_T1U_N11_GC_A09_D25_65-PadW24)") (class "Default")
      (node (ref "IC9") (pin "W24") (pinfunction "IO_L12N_T1U_N11_GC_A09_D25_65_W24") (pintype "bidirectional"))
    )
    (net (code "159") (name "unconnected-(IC9B-IO_L12P_T1U_N10_GC_A08_D24_65-PadV24)") (class "Default")
      (node (ref "IC9") (pin "V24") (pinfunction "IO_L12P_T1U_N10_GC_A08_D24_65_V24") (pintype "bidirectional"))
    )
    (net (code "160") (name "unconnected-(IC9B-IO_L13N_T2L_N1_GC_QBC_A07_D23_65-PadU24)") (class "Default")
      (node (ref "IC9") (pin "U24") (pinfunction "IO_L13N_T2L_N1_GC_QBC_A07_D23_65_U24") (pintype "bidirectional"))
    )
    (net (code "161") (name "unconnected-(IC9B-IO_L13P_T2L_N0_GC_QBC_A06_D22_65-PadT24)") (class "Default")
      (node (ref "IC9") (pin "T24") (pinfunction "IO_L13P_T2L_N0_GC_QBC_A06_D22_65_T24") (pintype "bidirectional"))
    )
    (net (code "162") (name "unconnected-(IC9B-IO_L14N_T2L_N3_GC_A05_D21_65-PadU25)") (class "Default")
      (node (ref "IC9") (pin "U25") (pinfunction "IO_L14N_T2L_N3_GC_A05_D21_65_U25") (pintype "bidirectional"))
    )
    (net (code "163") (name "unconnected-(IC9B-IO_L14P_T2L_N2_GC_A04_D20_65-PadT25)") (class "Default")
      (node (ref "IC9") (pin "T25") (pinfunction "IO_L14P_T2L_N2_GC_A04_D20_65_T25") (pintype "bidirectional"))
    )
    (net (code "164") (name "unconnected-(IC9B-IO_L15N_T2L_N5_AD11N_A03_D19_65-PadP24)") (class "Default")
      (node (ref "IC9") (pin "P24") (pinfunction "IO_L15N_T2L_N5_AD11N_A03_D19_65_P24") (pintype "bidirectional"))
    )
    (net (code "165") (name "unconnected-(IC9B-IO_L15P_T2L_N4_AD11P_A02_D18_65-PadN24)") (class "Default")
      (node (ref "IC9") (pin "N24") (pinfunction "IO_L15P_T2L_N4_AD11P_A02_D18_65_N24") (pintype "bidirectional"))
    )
    (net (code "166") (name "unconnected-(IC9B-IO_L16N_T2U_N7_QBC_AD3N_A01_D17_65-PadV26)") (class "Default")
      (node (ref "IC9") (pin "V26") (pinfunction "IO_L16N_T2U_N7_QBC_AD3N_A01_D17_65_V26") (pintype "bidirectional"))
    )
    (net (code "167") (name "unconnected-(IC9B-IO_L16P_T2U_N6_QBC_AD3P_A00_D16_65-PadU26)") (class "Default")
      (node (ref "IC9") (pin "U26") (pinfunction "IO_L16P_T2U_N6_QBC_AD3P_A00_D16_65_U26") (pintype "bidirectional"))
    )
    (net (code "168") (name "unconnected-(IC9B-IO_L17N_T2U_N9_AD10N_D15_65-PadP26)") (class "Default")
      (node (ref "IC9") (pin "P26") (pinfunction "IO_L17N_T2U_N9_AD10N_D15_65_P26") (pintype "bidirectional"))
    )
    (net (code "169") (name "unconnected-(IC9B-IO_L17P_T2U_N8_AD10P_D14_65-PadP25)") (class "Default")
      (node (ref "IC9") (pin "P25") (pinfunction "IO_L17P_T2U_N8_AD10P_D14_65_P25") (pintype "bidirectional"))
    )
    (net (code "170") (name "unconnected-(IC9B-IO_L18N_T2U_N11_AD2N_D13_65-PadR26)") (class "Default")
      (node (ref "IC9") (pin "R26") (pinfunction "IO_L18N_T2U_N11_AD2N_D13_65_R26") (pintype "bidirectional"))
    )
    (net (code "171") (name "unconnected-(IC9B-IO_L18P_T2U_N10_AD2P_D12_65-PadR25)") (class "Default")
      (node (ref "IC9") (pin "R25") (pinfunction "IO_L18P_T2U_N10_AD2P_D12_65_R25") (pintype "bidirectional"))
    )
    (net (code "172") (name "unconnected-(IC9B-IO_L19N_T3L_N1_DBC_AD9N_D11_65-PadR23)") (class "Default")
      (node (ref "IC9") (pin "R23") (pinfunction "IO_L19N_T3L_N1_DBC_AD9N_D11_65_R23") (pintype "bidirectional"))
    )
    (net (code "173") (name "unconnected-(IC9B-IO_L19P_T3L_N0_DBC_AD9P_D10_65-PadR22)") (class "Default")
      (node (ref "IC9") (pin "R22") (pinfunction "IO_L19P_T3L_N0_DBC_AD9P_D10_65_R22") (pintype "bidirectional"))
    )
    (net (code "174") (name "unconnected-(IC9B-IO_L20N_T3L_N3_AD1N_D09_65-PadP21)") (class "Default")
      (node (ref "IC9") (pin "P21") (pinfunction "IO_L20N_T3L_N3_AD1N_D09_65_P21") (pintype "bidirectional"))
    )
    (net (code "175") (name "unconnected-(IC9B-IO_L20P_T3L_N2_AD1P_D08_65-PadP20)") (class "Default")
      (node (ref "IC9") (pin "P20") (pinfunction "IO_L20P_T3L_N2_AD1P_D08_65_P20") (pintype "bidirectional"))
    )
    (net (code "176") (name "unconnected-(IC9B-IO_L21N_T3L_N5_AD8N_D07_65-PadR21)") (class "Default")
      (node (ref "IC9") (pin "R21") (pinfunction "IO_L21N_T3L_N5_AD8N_D07_65_R21") (pintype "bidirectional"))
    )
    (net (code "177") (name "unconnected-(IC9B-IO_L21P_T3L_N4_AD8P_D06_65-PadR20)") (class "Default")
      (node (ref "IC9") (pin "R20") (pinfunction "IO_L21P_T3L_N4_AD8P_D06_65_R20") (pintype "bidirectional"))
    )
    (net (code "178") (name "unconnected-(IC9B-IO_L22N_T3U_N7_DBC_AD0N_D05_65-PadP23)") (class "Default")
      (node (ref "IC9") (pin "P23") (pinfunction "IO_L22N_T3U_N7_DBC_AD0N_D05_65_P23") (pintype "bidirectional"))
    )
    (net (code "179") (name "unconnected-(IC9B-IO_L22P_T3U_N6_DBC_AD0P_D04_65-PadN23)") (class "Default")
      (node (ref "IC9") (pin "N23") (pinfunction "IO_L22P_T3U_N6_DBC_AD0P_D04_65_N23") (pintype "bidirectional"))
    )
    (net (code "180") (name "unconnected-(IC9B-IO_L23N_T3U_N9_PERSTN1_I2C_SDA_65-PadP19)") (class "Default")
      (node (ref "IC9") (pin "P19") (pinfunction "IO_L23N_T3U_N9_PERSTN1_I2C_SDA_65_P19") (pintype "bidirectional"))
    )
    (net (code "181") (name "unconnected-(IC9B-IO_L23P_T3U_N8_I2C_SCLK_65-PadN19)") (class "Default")
      (node (ref "IC9") (pin "N19") (pinfunction "IO_L23P_T3U_N8_I2C_SCLK_65_N19") (pintype "bidirectional"))
    )
    (net (code "182") (name "unconnected-(IC9B-IO_L24N_T3U_N11_DOUT_CSO_B_65-PadN22)") (class "Default")
      (node (ref "IC9") (pin "N22") (pinfunction "IO_L24N_T3U_N11_DOUT_CSO_B_65_N22") (pintype "bidirectional"))
    )
    (net (code "183") (name "unconnected-(IC9B-IO_L24P_T3U_N10_EMCCLK_65-PadN21)") (class "Default")
      (node (ref "IC9") (pin "N21") (pinfunction "IO_L24P_T3U_N10_EMCCLK_65_N21") (pintype "bidirectional"))
    )
    (net (code "184") (name "unconnected-(IC9B-IO_T0U_N12_VRP_A28_65-PadW21)") (class "Default")
      (node (ref "IC9") (pin "W21") (pinfunction "IO_T0U_N12_VRP_A28_65_W21") (pintype "bidirectional"))
    )
    (net (code "185") (name "unconnected-(IC9B-IO_T1U_N12_SMBALERT_65-PadAA23)") (class "Default")
      (node (ref "IC9") (pin "AA23") (pinfunction "IO_T1U_N12_SMBALERT_65_AA23") (pintype "bidirectional"))
    )
    (net (code "186") (name "unconnected-(IC9B-IO_T2U_N12_CSI_ADV_B_65-PadN26)") (class "Default")
      (node (ref "IC9") (pin "N26") (pinfunction "IO_T2U_N12_CSI_ADV_B_65_N26") (pintype "bidirectional"))
    )
    (net (code "187") (name "unconnected-(IC9B-IO_T3U_N12_PERSTN0_65-PadT19)") (class "Default")
      (node (ref "IC9") (pin "T19") (pinfunction "IO_T3U_N12_PERSTN0_65_T19") (pintype "bidirectional"))
    )
    (net (code "188") (name "unconnected-(IC9C-IO_L1N_T0L_N1_DBC_66-PadK18)") (class "Default")
      (node (ref "IC9") (pin "K18") (pinfunction "IO_L1N_T0L_N1_DBC_66_K18") (pintype "bidirectional"))
    )
    (net (code "189") (name "unconnected-(IC9C-IO_L1P_T0L_N0_DBC_66-PadL18)") (class "Default")
      (node (ref "IC9") (pin "L18") (pinfunction "IO_L1P_T0L_N0_DBC_66_L18") (pintype "bidirectional"))
    )
    (net (code "190") (name "unconnected-(IC9C-IO_L2N_T0L_N3_66-PadM21)") (class "Default")
      (node (ref "IC9") (pin "M21") (pinfunction "IO_L2N_T0L_N3_66_M21") (pintype "bidirectional"))
    )
    (net (code "191") (name "unconnected-(IC9C-IO_L2P_T0L_N2_66-PadM20)") (class "Default")
      (node (ref "IC9") (pin "M20") (pinfunction "IO_L2P_T0L_N2_66_M20") (pintype "bidirectional"))
    )
    (net (code "192") (name "unconnected-(IC9C-IO_L3N_T0L_N5_AD15N_66-PadJ20)") (class "Default")
      (node (ref "IC9") (pin "J20") (pinfunction "IO_L3N_T0L_N5_AD15N_66_J20") (pintype "bidirectional"))
    )
    (net (code "193") (name "unconnected-(IC9C-IO_L3P_T0L_N4_AD15P_66-PadJ19)") (class "Default")
      (node (ref "IC9") (pin "J19") (pinfunction "IO_L3P_T0L_N4_AD15P_66_J19") (pintype "bidirectional"))
    )
    (net (code "194") (name "unconnected-(IC9C-IO_L19P_T3L_N0_DBC_AD9P_66-PadE25)") (class "Default")
      (node (ref "IC9") (pin "E25") (pinfunction "IO_L19P_T3L_N0_DBC_AD9P_66_E25") (pintype "bidirectional"))
    )
    (net (code "195") (name "unconnected-(IC9C-IO_L23N_T3U_N9_66-PadC26)") (class "Default")
      (node (ref "IC9") (pin "C26") (pinfunction "IO_L23N_T3U_N9_66_C26") (pintype "bidirectional"))
    )
    (net (code "196") (name "unconnected-(IC9C-IO_L23P_T3U_N8_66-PadD26)") (class "Default")
      (node (ref "IC9") (pin "D26") (pinfunction "IO_L23P_T3U_N8_66_D26") (pintype "bidirectional"))
    )
    (net (code "197") (name "unconnected-(IC9C-IO_L24N_T3U_N11_66-PadB26)") (class "Default")
      (node (ref "IC9") (pin "B26") (pinfunction "IO_L24N_T3U_N11_66_B26") (pintype "bidirectional"))
    )
    (net (code "198") (name "unconnected-(IC9C-IO_L24P_T3U_N10_66-PadB25)") (class "Default")
      (node (ref "IC9") (pin "B25") (pinfunction "IO_L24P_T3U_N10_66_B25") (pintype "bidirectional"))
    )
    (net (code "199") (name "unconnected-(IC9C-IO_T0U_N12_VRP_66-PadM22)") (class "Default")
      (node (ref "IC9") (pin "M22") (pinfunction "IO_T0U_N12_VRP_66_M22") (pintype "bidirectional"))
    )
    (net (code "200") (name "unconnected-(IC9C-IO_T1U_N12_66-PadM24)") (class "Default")
      (node (ref "IC9") (pin "M24") (pinfunction "IO_T1U_N12_66_M24") (pintype "bidirectional"))
    )
    (net (code "201") (name "unconnected-(IC9C-IO_T2U_N12_66-PadG22)") (class "Default")
      (node (ref "IC9") (pin "G22") (pinfunction "IO_T2U_N12_66_G22") (pintype "bidirectional"))
    )
    (net (code "202") (name "unconnected-(IC9C-IO_T3U_N12_66-PadF22)") (class "Default")
      (node (ref "IC9") (pin "F22") (pinfunction "IO_T3U_N12_66_F22") (pintype "bidirectional"))
    )
    (net (code "203") (name "unconnected-(IC9D-IO_L6N_HDGC_AD6N_84-PadAB16)") (class "Default")
      (node (ref "IC9") (pin "AB16") (pinfunction "IO_L6N_HDGC_AD6N_84_AB16") (pintype "bidirectional"))
    )
    (net (code "204") (name "unconnected-(IC9D-IO_L6P_HDGC_AD6P_84-PadAB15)") (class "Default")
      (node (ref "IC9") (pin "AB15") (pinfunction "IO_L6P_HDGC_AD6P_84_AB15") (pintype "bidirectional"))
    )
    (net (code "205") (name "unconnected-(IC9D-IO_L7N_HDGC_AD5N_84-PadAA15)") (class "Default")
      (node (ref "IC9") (pin "AA15") (pinfunction "IO_L7N_HDGC_AD5N_84_AA15") (pintype "bidirectional"))
    )
    (net (code "206") (name "unconnected-(IC9D-IO_L7P_HDGC_AD5P_84-PadY15)") (class "Default")
      (node (ref "IC9") (pin "Y15") (pinfunction "IO_L7P_HDGC_AD5P_84_Y15") (pintype "bidirectional"))
    )
    (net (code "207") (name "unconnected-(IC9D-IO_L8N_HDGC_AD4N_84-PadAB14)") (class "Default")
      (node (ref "IC9") (pin "AB14") (pinfunction "IO_L8N_HDGC_AD4N_84_AB14") (pintype "bidirectional"))
    )
    (net (code "208") (name "unconnected-(IC9D-IO_L8P_HDGC_AD4P_84-PadAA14)") (class "Default")
      (node (ref "IC9") (pin "AA14") (pinfunction "IO_L8P_HDGC_AD4P_84_AA14") (pintype "bidirectional"))
    )
    (net (code "209") (name "unconnected-(IC9D-IO_L9N_AD3N_84-PadY16)") (class "Default")
      (node (ref "IC9") (pin "Y16") (pinfunction "IO_L9N_AD3N_84_Y16") (pintype "bidirectional"))
    )
    (net (code "210") (name "unconnected-(IC9D-IO_L9P_AD3P_84-PadW16)") (class "Default")
      (node (ref "IC9") (pin "W16") (pinfunction "IO_L9P_AD3P_84_W16") (pintype "bidirectional"))
    )
    (net (code "211") (name "unconnected-(IC9D-IO_L10N_AD2N_84-PadW15)") (class "Default")
      (node (ref "IC9") (pin "W15") (pinfunction "IO_L10N_AD2N_84_W15") (pintype "bidirectional"))
    )
    (net (code "212") (name "unconnected-(IC9D-IO_L10P_AD2P_84-PadW14)") (class "Default")
      (node (ref "IC9") (pin "W14") (pinfunction "IO_L10P_AD2P_84_W14") (pintype "bidirectional"))
    )
    (net (code "213") (name "unconnected-(IC9D-IO_L11N_AD1N_84-PadAA13)") (class "Default")
      (node (ref "IC9") (pin "AA13") (pinfunction "IO_L11N_AD1N_84_AA13") (pintype "bidirectional"))
    )
    (net (code "214") (name "unconnected-(IC9D-IO_L11P_AD1P_84-PadY13)") (class "Default")
      (node (ref "IC9") (pin "Y13") (pinfunction "IO_L11P_AD1P_84_Y13") (pintype "bidirectional"))
    )
    (net (code "215") (name "unconnected-(IC9D-IO_L12N_AD0N_84-PadW13)") (class "Default")
      (node (ref "IC9") (pin "W13") (pinfunction "IO_L12N_AD0N_84_W13") (pintype "bidirectional"))
    )
    (net (code "216") (name "unconnected-(IC9D-IO_L12P_AD0P_84-PadW12)") (class "Default")
      (node (ref "IC9") (pin "W12") (pinfunction "IO_L12P_AD0P_84_W12") (pintype "bidirectional"))
    )
    (net (code "217") (name "unconnected-(IC9F-IO_L1N_AD11N_86-PadH12)") (class "Default")
      (node (ref "IC9") (pin "H12") (pinfunction "IO_L1N_AD11N_86_H12") (pintype "bidirectional"))
    )
    (net (code "218") (name "unconnected-(IC9F-IO_L1P_AD11P_86-PadJ12)") (class "Default")
      (node (ref "IC9") (pin "J12") (pinfunction "IO_L1P_AD11P_86_J12") (pintype "bidirectional"))
    )
    (net (code "219") (name "unconnected-(IC9F-IO_L2P_AD10P_86-PadJ13)") (class "Default")
      (node (ref "IC9") (pin "J13") (pinfunction "IO_L2P_AD10P_86_J13") (pintype "bidirectional"))
    )
    (net (code "220") (name "unconnected-(IC9F-IO_L4P_AD8P_86-PadJ15)") (class "Default")
      (node (ref "IC9") (pin "J15") (pinfunction "IO_L4P_AD8P_86_J15") (pintype "bidirectional"))
    )
    (net (code "221") (name "unconnected-(IC9F-IO_L6N_HDGC_AD6N_86-PadF13)") (class "Default")
      (node (ref "IC9") (pin "F13") (pinfunction "IO_L6N_HDGC_AD6N_86_F13") (pintype "bidirectional"))
    )
    (net (code "222") (name "unconnected-(IC9F-IO_L6P_HDGC_AD6P_86-PadF14)") (class "Default")
      (node (ref "IC9") (pin "F14") (pinfunction "IO_L6P_HDGC_AD6P_86_F14") (pintype "bidirectional"))
    )
    (net (code "223") (name "unconnected-(IC9F-IO_L7P_HDGC_AD5P_86-PadE13)") (class "Default")
      (node (ref "IC9") (pin "E13") (pinfunction "IO_L7P_HDGC_AD5P_86_E13") (pintype "bidirectional"))
    )
    (net (code "224") (name "unconnected-(IC9F-IO_L8N_HDGC_AD4N_86-PadD13)") (class "Default")
      (node (ref "IC9") (pin "D13") (pinfunction "IO_L8N_HDGC_AD4N_86_D13") (pintype "bidirectional"))
    )
    (net (code "225") (name "unconnected-(IC9F-IO_L9N_AD3N_86-PadC13)") (class "Default")
      (node (ref "IC9") (pin "C13") (pinfunction "IO_L9N_AD3N_86_C13") (pintype "bidirectional"))
    )
    (net (code "226") (name "unconnected-(IC9F-IO_L9P_AD3P_86-PadC14)") (class "Default")
      (node (ref "IC9") (pin "C14") (pinfunction "IO_L9P_AD3P_86_C14") (pintype "bidirectional"))
    )
    (net (code "227") (name "unconnected-(IC9F-IO_L10N_AD2N_86-PadB12)") (class "Default")
      (node (ref "IC9") (pin "B12") (pinfunction "IO_L10N_AD2N_86_B12") (pintype "bidirectional"))
    )
    (net (code "228") (name "unconnected-(IC9F-IO_L10P_AD2P_86-PadC12)") (class "Default")
      (node (ref "IC9") (pin "C12") (pinfunction "IO_L10P_AD2P_86_C12") (pintype "bidirectional"))
    )
    (net (code "229") (name "unconnected-(IC9F-IO_L11N_AD1N_86-PadA12)") (class "Default")
      (node (ref "IC9") (pin "A12") (pinfunction "IO_L11N_AD1N_86_A12") (pintype "bidirectional"))
    )
    (net (code "230") (name "unconnected-(IC9F-IO_L11P_AD1P_86-PadA13)") (class "Default")
      (node (ref "IC9") (pin "A13") (pinfunction "IO_L11P_AD1P_86_A13") (pintype "bidirectional"))
    )
    (net (code "231") (name "unconnected-(IC9F-IO_L12N_AD0N_86-PadA14)") (class "Default")
      (node (ref "IC9") (pin "A14") (pinfunction "IO_L12N_AD0N_86_A14") (pintype "bidirectional"))
    )
    (net (code "232") (name "unconnected-(IC9F-IO_L12P_AD0P_86-PadB14)") (class "Default")
      (node (ref "IC9") (pin "B14") (pinfunction "IO_L12P_AD0P_86_B14") (pintype "bidirectional"))
    )
  )
)
